# DC-DC_15V_24V.net
KiCad netlist of a schematic drawn in Altium Designer
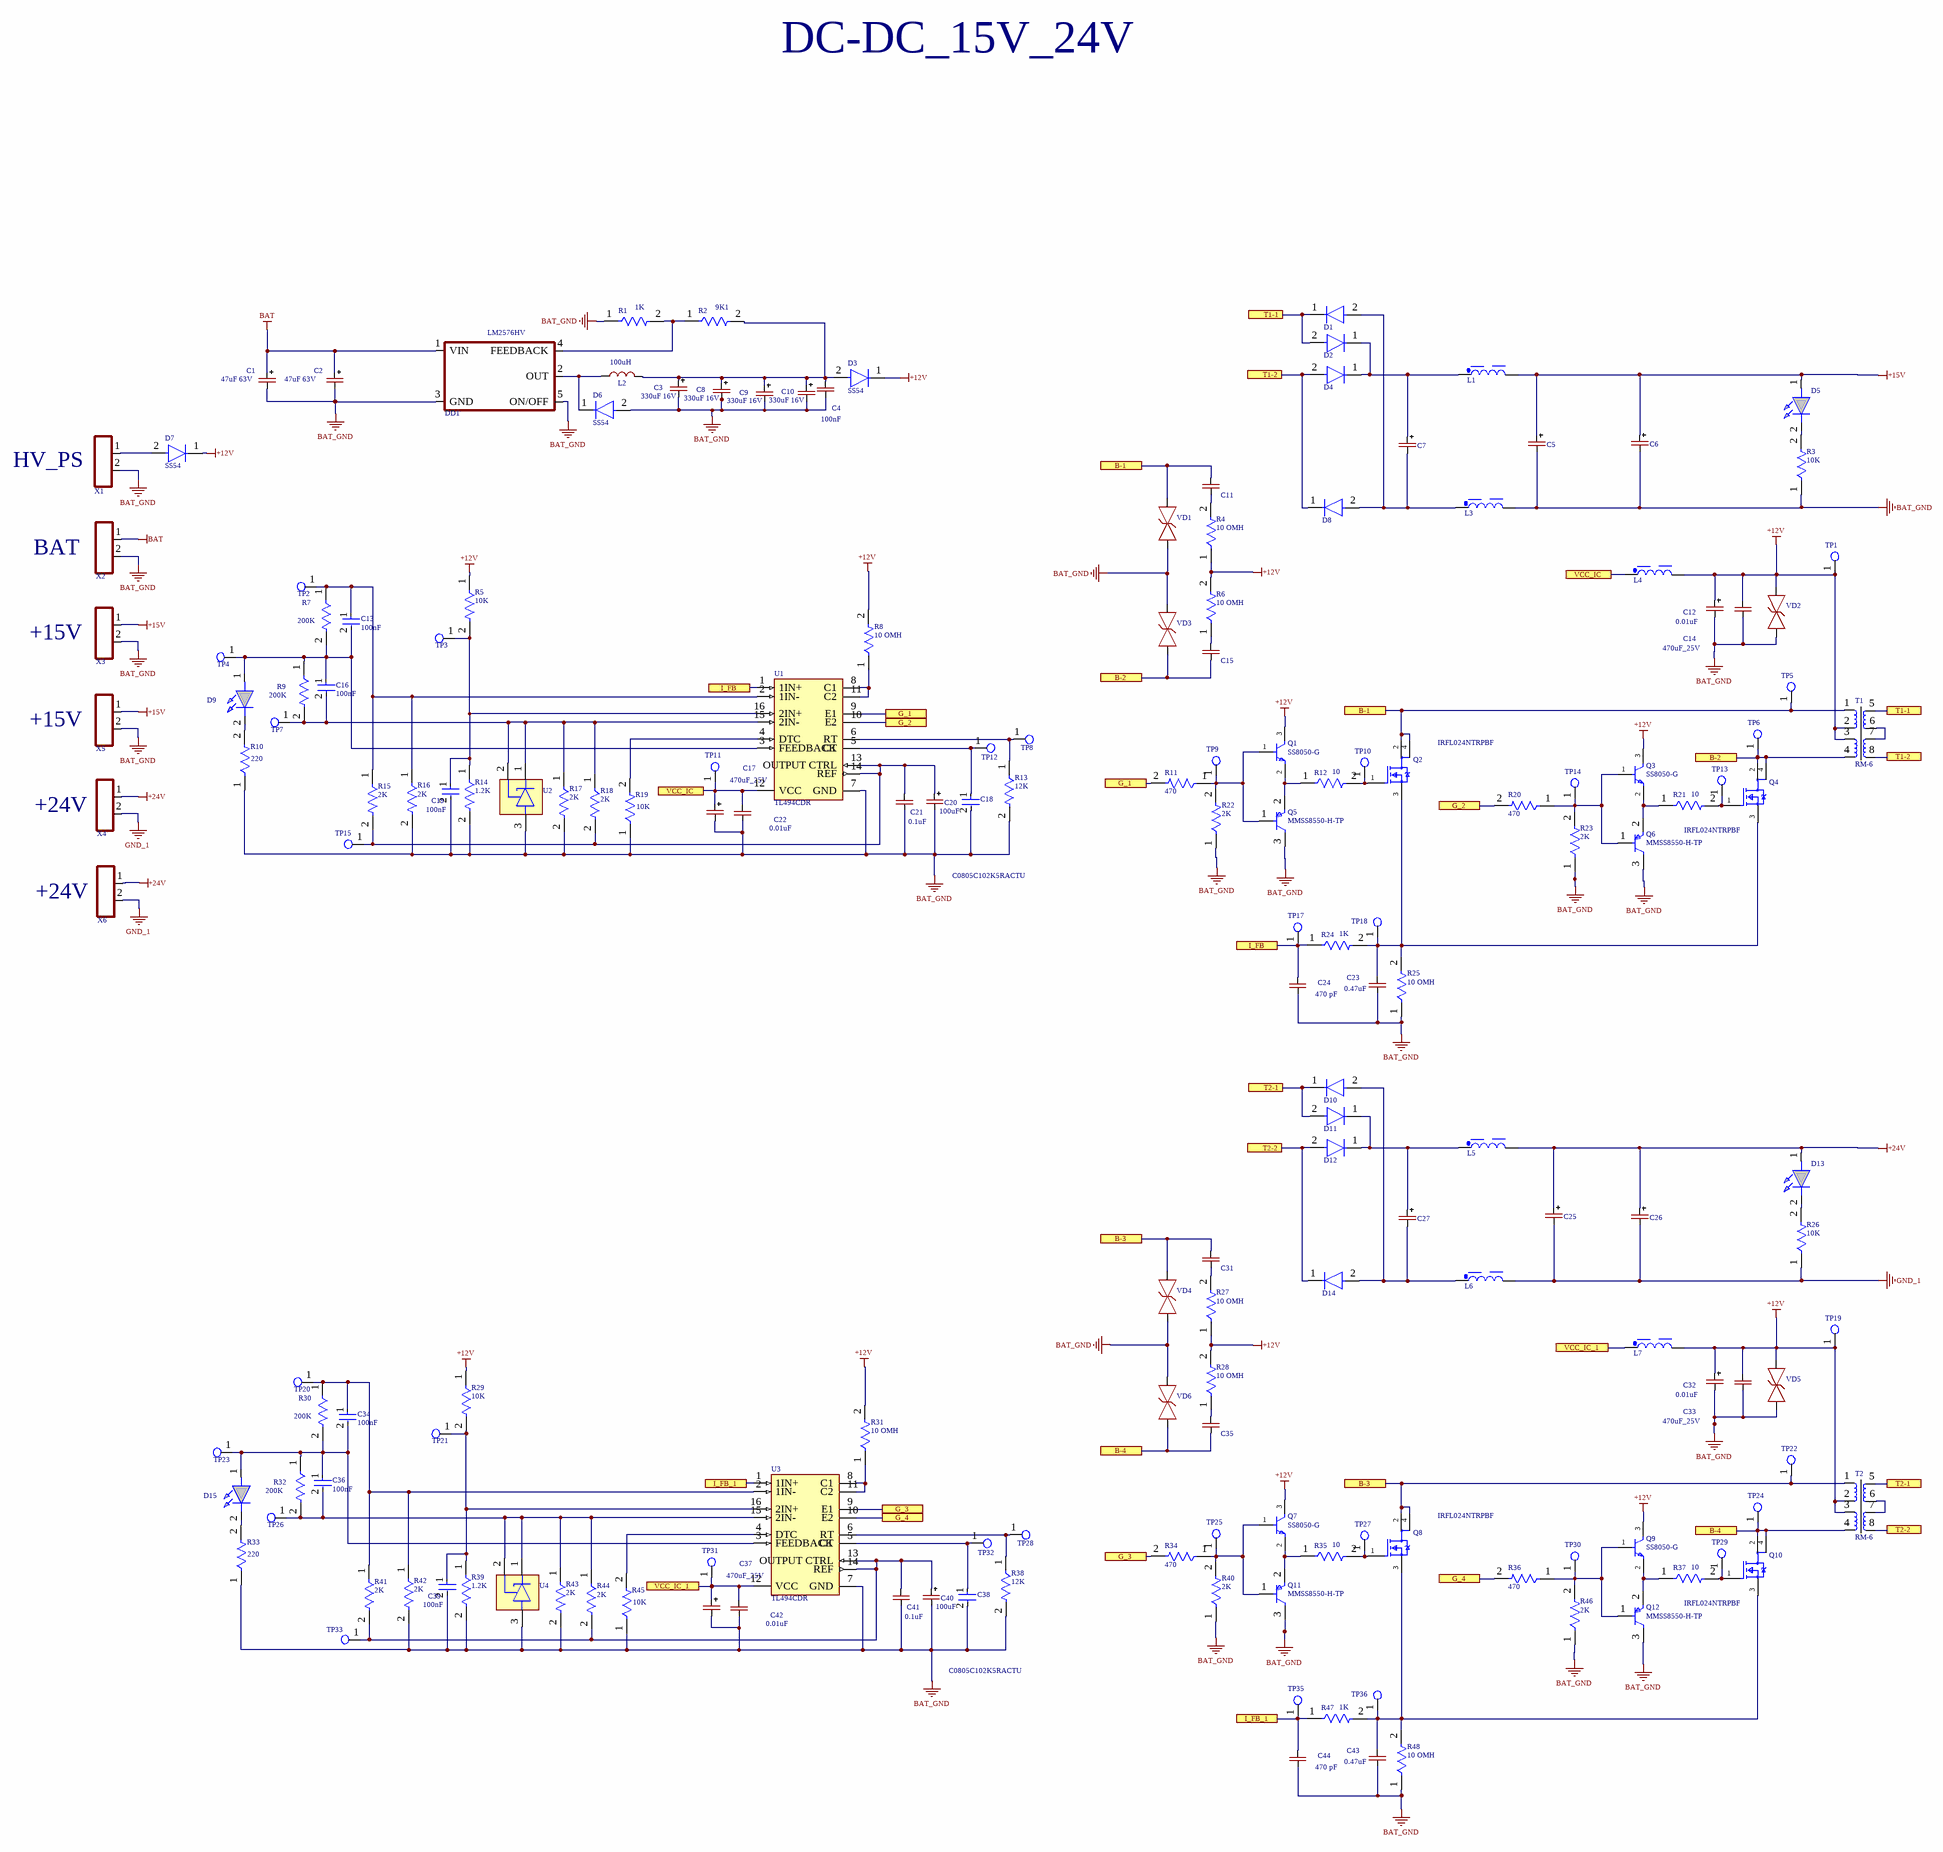
[diagram p0: DC-DC_15V_24V.SchDoc]

(export (version "E")
  (design (tool "Eeschema 10.0.6"))
  (components
    (comp (ref "C1")
      (value "47uF 63V")
      (footprint "CAP_SMD_Size_E")
      (libsource (lib "PASSIVE_COMPONENTS") (part "CAP_POL_SMD"))
    )
    (comp (ref "C2")
      (value "47uF 63V")
      (footprint "CAP_SMD_Size_E")
      (libsource (lib "PASSIVE_COMPONENTS") (part "CAP_POL_SMD"))
    )
    (comp (ref "C3")
      (value "330uF 16V")
      (footprint "CAP_SMD_Size_E")
      (libsource (lib "PASSIVE_COMPONENTS") (part "CAP_POL_SMD"))
    )
    (comp (ref "C4")
      (value "100nF")
      (footprint "CAP-0805")
      (description "1uF ±10% 50V X5R 0805 Multilayer Ceramic Capacitors MLCC - SMD/SMT RoHS")
      (fields (field (name "PART NUMBER") "CC0805KKX5R9BB105") (field (name "MANUFACTURER") "Yageo"))
      (libsource (lib "Database_Libs2") (part "CAP-NON-POLAR"))
    )
    (comp (ref "C5")
      (value "CAP-POLAR")
      (footprint "CAP_SMD_Size_G")
      (libsource (lib "PASSIVE_COMPONENTS") (part "CAP-POLAR"))
    )
    (comp (ref "C6")
      (value "CAP-POLAR")
      (footprint "CAP_SMD_Size_G")
      (libsource (lib "PASSIVE_COMPONENTS") (part "CAP-POLAR"))
    )
    (comp (ref "C7")
      (value "CAP-POLAR")
      (footprint "CAP_SMD_Size_G")
      (libsource (lib "PASSIVE_COMPONENTS") (part "CAP-POLAR"))
    )
    (comp (ref "C8")
      (value "330uF 16V")
      (footprint "CAP_SMD_Size_E")
      (libsource (lib "PASSIVE_COMPONENTS") (part "CAP_POL_SMD"))
    )
    (comp (ref "C9")
      (value "330uF 16V")
      (footprint "CAP_SMD_Size_E")
      (libsource (lib "PASSIVE_COMPONENTS") (part "CAP_POL_SMD"))
    )
    (comp (ref "C10")
      (value "330uF 16V")
      (footprint "CAP_SMD_Size_E")
      (libsource (lib "PASSIVE_COMPONENTS") (part "CAP_POL_SMD"))
    )
    (comp (ref "C11")
      (value "CAP-V")
      (footprint "CAP-V")
      (libsource (lib "PASSIVE_COMPONENTS") (part "CAP-V"))
    )
    (comp (ref "C12")
      (value "0.01uF")
      (footprint "CAP-0805")
      (libsource (lib "PASSIVE_COMPONENTS") (part "CAP-NON-POLAR"))
    )
    (comp (ref "C13")
      (value "100nF")
      (footprint "FP-C0805C-DN-MFG")
      (description "CAP CER 10000PF 50V X7R 0805")
      (fields
        (field (name "MANUFACTURER PART NUMBER") "C0805C103J5RACTU")
        (field (name "MANUFACTURER") "KEMET")
      )
      (libsource (lib "Altium Content Vault") (part "b4654b650e69147ec39a6b967a45e02"))
    )
    (comp (ref "C14")
      (value "470uF_25V")
      (footprint "CAP_SMD_Size_G")
      (libsource (lib "PASSIVE_COMPONENTS") (part "CAP-POLAR"))
    )
    (comp (ref "C15")
      (value "CAP-V")
      (footprint "CAP-V")
      (libsource (lib "PASSIVE_COMPONENTS") (part "CAP-V"))
    )
    (comp (ref "C16")
      (value "100nF")
      (footprint "FP-C0805C-DN-MFG")
      (description "CAP CER 10000PF 50V X7R 0805")
      (fields
        (field (name "MANUFACTURER PART NUMBER") "C0805C103J5RACTU")
        (field (name "MANUFACTURER") "KEMET")
      )
      (libsource (lib "Altium Content Vault") (part "b4654b650e69147ec39a6b967a45e02"))
    )
    (comp (ref "C17")
      (value "470uF_25V")
      (footprint "CAP_SMD_Size_G")
      (libsource (lib "PASSIVE_COMPONENTS") (part "CAP-POLAR"))
    )
    (comp (ref "C18")
      (value "C0805C102K5RACTU")
      (footprint "FP-C0805C-DN-MFG")
      (description "CAP CER 1000PF 50V X7R 0805")
      (fields
        (field (name "OCTOPART") "https://octopart.com/c0805c102k5ractu-kemet-93010")
        (field (name "TOLERANCE") "0.1")
      )
      (libsource (lib "Altium Content Vault") (part "b4654b650e69147ec39a6b967a45e02"))
    )
    (comp (ref "C19")
      (value "100nF")
      (footprint "FP-C0805C-DN-MFG")
      (description "CAP CER 10000PF 50V X7R 0805")
      (fields
        (field (name "MANUFACTURER PART NUMBER") "C0805C103J5RACTU")
        (field (name "MANUFACTURER") "KEMET")
      )
      (libsource (lib "Altium Content Vault") (part "b4654b650e69147ec39a6b967a45e02"))
    )
    (comp (ref "C20")
      (value "100uF")
      (footprint "CAP-TAN-D")
      (libsource (lib "PASSIVE_COMPONENTS") (part "CAP-POLAR"))
    )
    (comp (ref "C21")
      (value "0.1uF")
      (footprint "CAP-0805")
      (libsource (lib "PASSIVE_COMPONENTS") (part "CAP-NON-POLAR"))
    )
    (comp (ref "C22")
      (value "0.01uF")
      (footprint "CAP-0805")
      (libsource (lib "PASSIVE_COMPONENTS") (part "CAP-NON-POLAR"))
    )
    (comp (ref "C23")
      (value "0.47uF")
      (footprint "CAP-0805")
      (libsource (lib "PASSIVE_COMPONENTS") (part "CAP-NON-POLAR"))
    )
    (comp (ref "C24")
      (value "470 pF")
      (footprint "CAP-0805")
      (libsource (lib "PASSIVE_COMPONENTS") (part "CAP-NON-POLAR"))
    )
    (comp (ref "C25")
      (value "CAP-POLAR")
      (footprint "CAP_SMD_Size_G")
      (libsource (lib "PASSIVE_COMPONENTS") (part "CAP-POLAR"))
    )
    (comp (ref "C26")
      (value "CAP-POLAR")
      (footprint "CAP_SMD_Size_G")
      (libsource (lib "PASSIVE_COMPONENTS") (part "CAP-POLAR"))
    )
    (comp (ref "C27")
      (value "CAP-POLAR")
      (footprint "CAP_SMD_Size_G")
      (libsource (lib "PASSIVE_COMPONENTS") (part "CAP-POLAR"))
    )
    (comp (ref "C31")
      (value "CAP-V")
      (footprint "CAP-V")
      (libsource (lib "PASSIVE_COMPONENTS") (part "CAP-V"))
    )
    (comp (ref "C32")
      (value "0.01uF")
      (footprint "CAP-0805")
      (libsource (lib "PASSIVE_COMPONENTS") (part "CAP-NON-POLAR"))
    )
    (comp (ref "C33")
      (value "470uF_25V")
      (footprint "CAP_SMD_Size_G")
      (libsource (lib "PASSIVE_COMPONENTS") (part "CAP-POLAR"))
    )
    (comp (ref "C34")
      (value "100nF")
      (footprint "FP-C0805C-DN-MFG")
      (description "CAP CER 10000PF 50V X7R 0805")
      (fields
        (field (name "MANUFACTURER PART NUMBER") "C0805C103J5RACTU")
        (field (name "MANUFACTURER") "KEMET")
      )
      (libsource (lib "Altium Content Vault") (part "b4654b650e69147ec39a6b967a45e02"))
    )
    (comp (ref "C35")
      (value "CAP-V")
      (footprint "CAP-V")
      (libsource (lib "PASSIVE_COMPONENTS") (part "CAP-V"))
    )
    (comp (ref "C36")
      (value "100nF")
      (footprint "FP-C0805C-DN-MFG")
      (description "CAP CER 10000PF 50V X7R 0805")
      (fields
        (field (name "MANUFACTURER PART NUMBER") "C0805C103J5RACTU")
        (field (name "MANUFACTURER") "KEMET")
      )
      (libsource (lib "Altium Content Vault") (part "b4654b650e69147ec39a6b967a45e02"))
    )
    (comp (ref "C37")
      (value "470uF_25V")
      (footprint "CAP_SMD_Size_G")
      (libsource (lib "PASSIVE_COMPONENTS") (part "CAP-POLAR"))
    )
    (comp (ref "C38")
      (value "C0805C102K5RACTU")
      (footprint "FP-C0805C-DN-MFG")
      (description "CAP CER 1000PF 50V X7R 0805")
      (fields
        (field (name "OCTOPART") "https://octopart.com/c0805c102k5ractu-kemet-93010")
        (field (name "TOLERANCE") "0.1")
      )
      (libsource (lib "Altium Content Vault") (part "b4654b650e69147ec39a6b967a45e02"))
    )
    (comp (ref "C39")
      (value "100nF")
      (footprint "FP-C0805C-DN-MFG")
      (description "CAP CER 10000PF 50V X7R 0805")
      (fields
        (field (name "MANUFACTURER PART NUMBER") "C0805C103J5RACTU")
        (field (name "MANUFACTURER") "KEMET")
      )
      (libsource (lib "Altium Content Vault") (part "b4654b650e69147ec39a6b967a45e02"))
    )
    (comp (ref "C40")
      (value "100uF")
      (footprint "CAP-TAN-D")
      (libsource (lib "PASSIVE_COMPONENTS") (part "CAP-POLAR"))
    )
    (comp (ref "C41")
      (value "0.1uF")
      (footprint "CAP-0805")
      (libsource (lib "PASSIVE_COMPONENTS") (part "CAP-NON-POLAR"))
    )
    (comp (ref "C42")
      (value "0.01uF")
      (footprint "CAP-0805")
      (libsource (lib "PASSIVE_COMPONENTS") (part "CAP-NON-POLAR"))
    )
    (comp (ref "C43")
      (value "0.47uF")
      (footprint "CAP-0805")
      (libsource (lib "PASSIVE_COMPONENTS") (part "CAP-NON-POLAR"))
    )
    (comp (ref "C44")
      (value "470 pF")
      (footprint "CAP-0805")
      (libsource (lib "PASSIVE_COMPONENTS") (part "CAP-NON-POLAR"))
    )
    (comp (ref "D1") (value "US1G") (footprint "DO-214AA") (libsource (lib "Diodes") (part "US1G")))
    (comp (ref "D2") (value "US1G") (footprint "DO-214AA") (libsource (lib "Diodes") (part "US1G")))
    (comp (ref "D3")
      (value "SS54")
      (footprint "DO214-AB")
      (description "ES3D-DO214AB")
      (libsource (lib "Diodes") (part "ES3D-DO214AB"))
    )
    (comp (ref "D4") (value "US1G") (footprint "DO-214AA") (libsource (lib "Diodes") (part "US1G")))
    (comp (ref "D5")
      (value "151031YS06000")
      (footprint "LED_RED")
      (description "WURTH ELEKTRONIK - 151031YS06000 - LED, Yellow, Through Hole, T-1 (3mm), 30 mA, 2 V, 590 nm")
      (fields (field (name "MOUSER PART NUMBER") "710-151031YS06000"))
      (libsource (lib "Optic-LED") (part "LED"))
    )
    (comp (ref "D6")
      (value "SS54")
      (footprint "DO214-AB")
      (description "ES3D-DO214AB")
      (libsource (lib "Diodes") (part "ES3D-DO214AB"))
    )
    (comp (ref "D7")
      (value "SS54")
      (footprint "DO214-AB")
      (description "ES3D-DO214AB")
      (libsource (lib "Diodes") (part "ES3D-DO214AB"))
    )
    (comp (ref "D8") (value "US1G") (footprint "DO-214AA") (libsource (lib "Diodes") (part "US1G")))
    (comp (ref "D9")
      (value "151031YS06000")
      (footprint "LED_RED")
      (description "WURTH ELEKTRONIK - 151031YS06000 - LED, Yellow, Through Hole, T-1 (3mm), 30 mA, 2 V, 590 nm")
      (fields (field (name "MOUSER PART NUMBER") "710-151031YS06000"))
      (libsource (lib "Optic-LED") (part "LED"))
    )
    (comp (ref "D10") (value "US1G") (footprint "DO-214AA") (libsource (lib "Diodes") (part "US1G")))
    (comp (ref "D11") (value "US1G") (footprint "DO-214AA") (libsource (lib "Diodes") (part "US1G")))
    (comp (ref "D12") (value "US1G") (footprint "DO-214AA") (libsource (lib "Diodes") (part "US1G")))
    (comp (ref "D13")
      (value "151031YS06000")
      (footprint "LED_RED")
      (description "WURTH ELEKTRONIK - 151031YS06000 - LED, Yellow, Through Hole, T-1 (3mm), 30 mA, 2 V, 590 nm")
      (fields (field (name "MOUSER PART NUMBER") "710-151031YS06000"))
      (libsource (lib "Optic-LED") (part "LED"))
    )
    (comp (ref "D14") (value "US1G") (footprint "DO-214AA") (libsource (lib "Diodes") (part "US1G")))
    (comp (ref "D15")
      (value "151031YS06000")
      (footprint "LED_RED")
      (description "WURTH ELEKTRONIK - 151031YS06000 - LED, Yellow, Through Hole, T-1 (3mm), 30 mA, 2 V, 590 nm")
      (fields (field (name "MOUSER PART NUMBER") "710-151031YS06000"))
      (libsource (lib "Optic-LED") (part "LED"))
    )
    (comp (ref "DD1")
      (value "LM2576HV")
      (footprint "TO-263-5")
      (libsource (lib "LM2576HV") (part "LM2576HV"))
    )
    (comp (ref "L1")
      (value "390µH, 0.38A")
      (footprint "WE-PD2_7850")
      (description "WE-PD2 SMT Power Inductor, size 7850, 390µH, 0.38A, 1.77Ω")
      (fields
        (field (name "MANUFACTURER PART NUMBER") "744775239")
        (field (name "MANUFACTURER") "Wurth Elektronik")
      )
      (libsource (lib "WE-PD2 (rev22d)") (part "744775239"))
    )
    (comp (ref "L2") (value "100uH") (footprint "CDRH127") (libsource (lib "CDRH127") (part "IND-CONST")))
    (comp (ref "L3")
      (value "390µH, 0.38A")
      (footprint "WE-PD2_7850")
      (description "WE-PD2 SMT Power Inductor, size 7850, 390µH, 0.38A, 1.77Ω")
      (fields
        (field (name "MANUFACTURER PART NUMBER") "744775239")
        (field (name "MANUFACTURER") "Wurth Elektronik")
      )
      (libsource (lib "WE-PD2 (rev22d)") (part "744775239"))
    )
    (comp (ref "L4")
      (value "390µH, 0.38A")
      (footprint "WE-PD2_7850")
      (description "WE-PD2 SMT Power Inductor, size 7850, 390µH, 0.38A, 1.77Ω")
      (fields
        (field (name "MANUFACTURER PART NUMBER") "744775239")
        (field (name "MANUFACTURER") "Wurth Elektronik")
      )
      (libsource (lib "WE-PD2 (rev22d)") (part "744775239"))
    )
    (comp (ref "L5")
      (value "390µH, 0.38A")
      (footprint "WE-PD2_7850")
      (description "WE-PD2 SMT Power Inductor, size 7850, 390µH, 0.38A, 1.77Ω")
      (fields
        (field (name "MANUFACTURER PART NUMBER") "744775239")
        (field (name "MANUFACTURER") "Wurth Elektronik")
      )
      (libsource (lib "WE-PD2 (rev22d)") (part "744775239"))
    )
    (comp (ref "L6")
      (value "390µH, 0.38A")
      (footprint "WE-PD2_7850")
      (description "WE-PD2 SMT Power Inductor, size 7850, 390µH, 0.38A, 1.77Ω")
      (fields
        (field (name "MANUFACTURER PART NUMBER") "744775239")
        (field (name "MANUFACTURER") "Wurth Elektronik")
      )
      (libsource (lib "WE-PD2 (rev22d)") (part "744775239"))
    )
    (comp (ref "L7")
      (value "390µH, 0.38A")
      (footprint "WE-PD2_7850")
      (description "WE-PD2 SMT Power Inductor, size 7850, 390µH, 0.38A, 1.77Ω")
      (fields
        (field (name "MANUFACTURER PART NUMBER") "744775239")
        (field (name "MANUFACTURER") "Wurth Elektronik")
      )
      (libsource (lib "WE-PD2 (rev22d)") (part "744775239"))
    )
    (comp (ref "Q1")
      (value "SS8050-G")
      (footprint "FP-SS8050-G-MFG")
      (description "NPN TRANSISTOR 1.5A 40V SOT-23 R")
      (libsource (lib "Altium Content Vault") (part "2a1388f82443b098dcd57d24ac7632d"))
    )
    (comp (ref "Q2")
      (value "IRFL024NTRPBF")
      (footprint "FP-PG-SOT223-3-IPC_B")
      (description "MOSFET N-CH 55V 2.8A SOT223")
      (libsource (lib "Altium Content Vault") (part "7f70c8421781a2c4d0598199639518f"))
    )
    (comp (ref "Q3")
      (value "SS8050-G")
      (footprint "FP-SS8050-G-MFG")
      (description "NPN TRANSISTOR 1.5A 40V SOT-23 R")
      (libsource (lib "Altium Content Vault") (part "2a1388f82443b098dcd57d24ac7632d"))
    )
    (comp (ref "Q4")
      (value "IRFL024NTRPBF")
      (footprint "FP-PG-SOT223-3-IPC_B")
      (description "MOSFET N-CH 55V 2.8A SOT223")
      (libsource (lib "Altium Content Vault") (part "7f70c8421781a2c4d0598199639518f"))
    )
    (comp (ref "Q5")
      (value "MMSS8550-H-TP")
      (footprint "FP-SOT-23-IPC_B")
      (description "TRANS PNP 25V 1.5A SOT23")
      (libsource (lib "Altium Content Vault") (part "0e8486ed3b47d9c69b8404ba87cf0f7"))
    )
    (comp (ref "Q6")
      (value "MMSS8550-H-TP")
      (footprint "FP-SOT-23-IPC_B")
      (description "TRANS PNP 25V 1.5A SOT23")
      (libsource (lib "Altium Content Vault") (part "0e8486ed3b47d9c69b8404ba87cf0f7"))
    )
    (comp (ref "Q7")
      (value "SS8050-G")
      (footprint "FP-SS8050-G-MFG")
      (description "NPN TRANSISTOR 1.5A 40V SOT-23 R")
      (libsource (lib "Altium Content Vault") (part "2a1388f82443b098dcd57d24ac7632d"))
    )
    (comp (ref "Q8")
      (value "IRFL024NTRPBF")
      (footprint "FP-PG-SOT223-3-IPC_B")
      (description "MOSFET N-CH 55V 2.8A SOT223")
      (libsource (lib "Altium Content Vault") (part "7f70c8421781a2c4d0598199639518f"))
    )
    (comp (ref "Q9")
      (value "SS8050-G")
      (footprint "FP-SS8050-G-MFG")
      (description "NPN TRANSISTOR 1.5A 40V SOT-23 R")
      (libsource (lib "Altium Content Vault") (part "2a1388f82443b098dcd57d24ac7632d"))
    )
    (comp (ref "Q10")
      (value "IRFL024NTRPBF")
      (footprint "FP-PG-SOT223-3-IPC_B")
      (description "MOSFET N-CH 55V 2.8A SOT223")
      (libsource (lib "Altium Content Vault") (part "7f70c8421781a2c4d0598199639518f"))
    )
    (comp (ref "Q11")
      (value "MMSS8550-H-TP")
      (footprint "FP-SOT-23-IPC_B")
      (description "TRANS PNP 25V 1.5A SOT23")
      (libsource (lib "Altium Content Vault") (part "0e8486ed3b47d9c69b8404ba87cf0f7"))
    )
    (comp (ref "Q12")
      (value "MMSS8550-H-TP")
      (footprint "FP-SOT-23-IPC_B")
      (description "TRANS PNP 25V 1.5A SOT23")
      (libsource (lib "Altium Content Vault") (part "0e8486ed3b47d9c69b8404ba87cf0f7"))
    )
    (comp (ref "R1")
      (value "1K")
      (footprint "RES-0805")
      (description "10K")
      (libsource (lib "PASSIVE_COMPONENTS") (part "RES-CONST"))
    )
    (comp (ref "R2")
      (value "9K1")
      (footprint "RES-0805")
      (description "10K")
      (libsource (lib "PASSIVE_COMPONENTS") (part "RES-CONST"))
    )
    (comp (ref "R3")
      (value "10K")
      (footprint "RES-0805")
      (libsource (lib "PASSIVE_COMPONENTS") (part "RES-CONST"))
    )
    (comp (ref "R4")
      (value "10 OMH")
      (footprint "RES-1206")
      (libsource (lib "PASSIVE_COMPONENTS") (part "RES-CONST"))
    )
    (comp (ref "R5")
      (value "10K")
      (footprint "FP-CRCW0805-e3-MFG")
      (description "RES Thick Film, 2kΩ, 1%, 0.125W, 100ppm/°C, 0805")
      (fields (field (name "TOLERANCE") "1%"))
      (libsource (lib "Pasive_components") (part "CMP-2001-04908-2"))
    )
    (comp (ref "R6")
      (value "10 OMH")
      (footprint "RES-1206")
      (libsource (lib "PASSIVE_COMPONENTS") (part "RES-CONST"))
    )
    (comp (ref "R7")
      (value "200K")
      (footprint "FP-CRCW0805-e3-MFG")
      (description "RES Thick Film, 2kΩ, 1%, 0.125W, 100ppm/°C, 0805")
      (fields (field (name "TOLERANCE") "1%"))
      (libsource (lib "Pasive_components") (part "CMP-2001-04908-2"))
    )
    (comp (ref "R8")
      (value "10 OMH")
      (footprint "RES-1206")
      (libsource (lib "PASSIVE_COMPONENTS") (part "RES-CONST"))
    )
    (comp (ref "R9")
      (value "200K")
      (footprint "FP-CRCW0805-e3-MFG")
      (description "RES Thick Film, 2kΩ, 1%, 0.125W, 100ppm/°C, 0805")
      (fields (field (name "TOLERANCE") "1%"))
      (libsource (lib "Pasive_components") (part "CMP-2001-04908-2"))
    )
    (comp (ref "R10")
      (value "220")
      (footprint "RES-0805")
      (libsource (lib "PASSIVE_COMPONENTS") (part "RES-CONST"))
    )
    (comp (ref "R11")
      (value "470")
      (footprint "RES-0805")
      (libsource (lib "PASSIVE_COMPONENTS") (part "RES-CONST"))
    )
    (comp (ref "R12")
      (value "10")
      (footprint "RES-0805")
      (libsource (lib "PASSIVE_COMPONENTS") (part "RES-CONST"))
    )
    (comp (ref "R13")
      (value "12K")
      (footprint "FP-CRCW0805-e3-MFG")
      (description "RES Thick Film, 12kΩ, 1%, 0.125W, 100ppm/°C, 0805")
      (fields (field (name "TOLERANCE") "1%"))
      (libsource (lib "Pasive_components") (part "CMP-2001-04908-2"))
    )
    (comp (ref "R14")
      (value "1.2K")
      (footprint "FP-CRCW0805-e3-MFG")
      (description "RES Thick Film, 2kΩ, 1%, 0.125W, 100ppm/°C, 0805")
      (fields (field (name "TOLERANCE") "1%"))
      (libsource (lib "Pasive_components") (part "CMP-2001-04908-2"))
    )
    (comp (ref "R15")
      (value "2K")
      (footprint "FP-CRCW0805-e3-MFG")
      (description "RES Thick Film, 2kΩ, 1%, 0.125W, 100ppm/°C, 0805")
      (fields (field (name "TOLERANCE") "1%"))
      (libsource (lib "Pasive_components") (part "CMP-2001-04908-2"))
    )
    (comp (ref "R16")
      (value "2K")
      (footprint "FP-CRCW0805-e3-MFG")
      (description "RES Thick Film, 82kΩ, 1%, 0.125W, 100ppm/°C, 0805")
      (fields (field (name "TOLERANCE") "1%"))
      (libsource (lib "Pasive_components") (part "CMP-2001-04908-2"))
    )
    (comp (ref "R17")
      (value "2K")
      (footprint "FP-CRCW0805-e3-MFG")
      (description "RES Thick Film, 2kΩ, 1%, 0.125W, 100ppm/°C, 0805")
      (fields (field (name "TOLERANCE") "1%"))
      (libsource (lib "Pasive_components") (part "CMP-2001-04908-2"))
    )
    (comp (ref "R18")
      (value "2K")
      (footprint "FP-CRCW0805-e3-MFG")
      (description "RES Thick Film, 2kΩ, 1%, 0.125W, 100ppm/°C, 0805")
      (fields (field (name "TOLERANCE") "1%"))
      (libsource (lib "Pasive_components") (part "CMP-2001-04908-2"))
    )
    (comp (ref "R19")
      (value "10K")
      (footprint "RES-0805")
      (libsource (lib "PASSIVE_COMPONENTS") (part "RES-CONST"))
    )
    (comp (ref "R20")
      (value "470")
      (footprint "RES-0805")
      (libsource (lib "PASSIVE_COMPONENTS") (part "RES-CONST"))
    )
    (comp (ref "R21")
      (value "10")
      (footprint "RES-0805")
      (libsource (lib "PASSIVE_COMPONENTS") (part "RES-CONST"))
    )
    (comp (ref "R22")
      (value "2K")
      (footprint "RES-0805")
      (libsource (lib "PASSIVE_COMPONENTS") (part "RES-CONST"))
    )
    (comp (ref "R23")
      (value "2K")
      (footprint "RES-0805")
      (libsource (lib "PASSIVE_COMPONENTS") (part "RES-CONST"))
    )
    (comp (ref "R24")
      (value "1K")
      (footprint "RES-0805")
      (libsource (lib "PASSIVE_COMPONENTS") (part "RES-CONST"))
    )
    (comp (ref "R25")
      (value "10 OMH")
      (footprint "RES-2512")
      (libsource (lib "PASSIVE_COMPONENTS") (part "RES-CONST"))
    )
    (comp (ref "R26")
      (value "10K")
      (footprint "RES-0805")
      (libsource (lib "PASSIVE_COMPONENTS") (part "RES-CONST"))
    )
    (comp (ref "R27")
      (value "10 OMH")
      (footprint "RES-1206")
      (libsource (lib "PASSIVE_COMPONENTS") (part "RES-CONST"))
    )
    (comp (ref "R28")
      (value "10 OMH")
      (footprint "RES-1206")
      (libsource (lib "PASSIVE_COMPONENTS") (part "RES-CONST"))
    )
    (comp (ref "R29")
      (value "10K")
      (footprint "FP-CRCW0805-e3-MFG")
      (description "RES Thick Film, 2kΩ, 1%, 0.125W, 100ppm/°C, 0805")
      (fields (field (name "TOLERANCE") "1%"))
      (libsource (lib "Pasive_components") (part "CMP-2001-04908-2"))
    )
    (comp (ref "R30")
      (value "200K")
      (footprint "FP-CRCW0805-e3-MFG")
      (description "RES Thick Film, 2kΩ, 1%, 0.125W, 100ppm/°C, 0805")
      (fields (field (name "TOLERANCE") "1%"))
      (libsource (lib "Pasive_components") (part "CMP-2001-04908-2"))
    )
    (comp (ref "R31")
      (value "10 OMH")
      (footprint "RES-1206")
      (libsource (lib "PASSIVE_COMPONENTS") (part "RES-CONST"))
    )
    (comp (ref "R32")
      (value "200K")
      (footprint "FP-CRCW0805-e3-MFG")
      (description "RES Thick Film, 2kΩ, 1%, 0.125W, 100ppm/°C, 0805")
      (fields (field (name "TOLERANCE") "1%"))
      (libsource (lib "Pasive_components") (part "CMP-2001-04908-2"))
    )
    (comp (ref "R33")
      (value "220")
      (footprint "RES-0805")
      (libsource (lib "PASSIVE_COMPONENTS") (part "RES-CONST"))
    )
    (comp (ref "R34")
      (value "470")
      (footprint "RES-0805")
      (libsource (lib "PASSIVE_COMPONENTS") (part "RES-CONST"))
    )
    (comp (ref "R35")
      (value "10")
      (footprint "RES-0805")
      (libsource (lib "PASSIVE_COMPONENTS") (part "RES-CONST"))
    )
    (comp (ref "R36")
      (value "470")
      (footprint "RES-0805")
      (libsource (lib "PASSIVE_COMPONENTS") (part "RES-CONST"))
    )
    (comp (ref "R37")
      (value "10")
      (footprint "RES-0805")
      (libsource (lib "PASSIVE_COMPONENTS") (part "RES-CONST"))
    )
    (comp (ref "R38")
      (value "12K")
      (footprint "FP-CRCW0805-e3-MFG")
      (description "RES Thick Film, 12kΩ, 1%, 0.125W, 100ppm/°C, 0805")
      (fields (field (name "TOLERANCE") "1%"))
      (libsource (lib "Pasive_components") (part "CMP-2001-04908-2"))
    )
    (comp (ref "R39")
      (value "1.2K")
      (footprint "FP-CRCW0805-e3-MFG")
      (description "RES Thick Film, 2kΩ, 1%, 0.125W, 100ppm/°C, 0805")
      (fields (field (name "TOLERANCE") "1%"))
      (libsource (lib "Pasive_components") (part "CMP-2001-04908-2"))
    )
    (comp (ref "R40")
      (value "2K")
      (footprint "RES-0805")
      (libsource (lib "PASSIVE_COMPONENTS") (part "RES-CONST"))
    )
    (comp (ref "R41")
      (value "2K")
      (footprint "FP-CRCW0805-e3-MFG")
      (description "RES Thick Film, 2kΩ, 1%, 0.125W, 100ppm/°C, 0805")
      (fields (field (name "TOLERANCE") "1%"))
      (libsource (lib "Pasive_components") (part "CMP-2001-04908-2"))
    )
    (comp (ref "R42")
      (value "2K")
      (footprint "FP-CRCW0805-e3-MFG")
      (description "RES Thick Film, 82kΩ, 1%, 0.125W, 100ppm/°C, 0805")
      (fields (field (name "TOLERANCE") "1%"))
      (libsource (lib "Pasive_components") (part "CMP-2001-04908-2"))
    )
    (comp (ref "R43")
      (value "2K")
      (footprint "FP-CRCW0805-e3-MFG")
      (description "RES Thick Film, 2kΩ, 1%, 0.125W, 100ppm/°C, 0805")
      (fields (field (name "TOLERANCE") "1%"))
      (libsource (lib "Pasive_components") (part "CMP-2001-04908-2"))
    )
    (comp (ref "R44")
      (value "2K")
      (footprint "FP-CRCW0805-e3-MFG")
      (description "RES Thick Film, 2kΩ, 1%, 0.125W, 100ppm/°C, 0805")
      (fields (field (name "TOLERANCE") "1%"))
      (libsource (lib "Pasive_components") (part "CMP-2001-04908-2"))
    )
    (comp (ref "R45")
      (value "10K")
      (footprint "RES-0805")
      (libsource (lib "PASSIVE_COMPONENTS") (part "RES-CONST"))
    )
    (comp (ref "R46")
      (value "2K")
      (footprint "RES-0805")
      (libsource (lib "PASSIVE_COMPONENTS") (part "RES-CONST"))
    )
    (comp (ref "R47")
      (value "1K")
      (footprint "RES-0805")
      (libsource (lib "PASSIVE_COMPONENTS") (part "RES-CONST"))
    )
    (comp (ref "R48")
      (value "10 OMH")
      (footprint "RES-2512")
      (libsource (lib "PASSIVE_COMPONENTS") (part "RES-CONST"))
    )
    (comp (ref "T1")
      (value "RM-6")
      (footprint "TRANS_RM6")
      (libsource (lib "Transformers") (part "RM_6_12-12-18-18"))
    )
    (comp (ref "T2")
      (value "RM-6")
      (footprint "TRANS_RM6")
      (libsource (lib "Transformers") (part "RM_6_12-12-18-18"))
    )
    (comp (ref "TP1")
      (value "~")
      (footprint "Test_Point")
      (description "Test_Point")
      (libsource (lib "Connectors") (part "TP_PCB?"))
    )
    (comp (ref "TP2")
      (value "Test_Point_PCB")
      (footprint "Test_Point")
      (description "Test_Point")
      (libsource (lib "Test_Point") (part "TP_PCB?"))
    )
    (comp (ref "TP3")
      (value "Test_Point_PCB")
      (footprint "Test_Point")
      (description "Test_Point")
      (libsource (lib "Test_Point") (part "TP_PCB?"))
    )
    (comp (ref "TP4")
      (value "Test_Point_PCB")
      (footprint "Test_Point")
      (description "Test_Point")
      (libsource (lib "Test_Point") (part "TP_PCB?"))
    )
    (comp (ref "TP5")
      (value "~")
      (footprint "Test_Point")
      (description "Test_Point")
      (libsource (lib "Connectors") (part "TP_PCB?"))
    )
    (comp (ref "TP6")
      (value "~")
      (footprint "Test_Point")
      (description "Test_Point")
      (libsource (lib "Connectors") (part "TP_PCB?"))
    )
    (comp (ref "TP7")
      (value "~")
      (footprint "Test_Point")
      (description "Test_Point")
      (libsource (lib "Connectors") (part "TP_PCB?"))
    )
    (comp (ref "TP8")
      (value "~")
      (footprint "Test_Point")
      (description "Test_Point")
      (libsource (lib "Connectors") (part "TP_PCB?"))
    )
    (comp (ref "TP9")
      (value "~")
      (footprint "Test_Point")
      (description "Test_Point")
      (libsource (lib "Connectors") (part "TP_PCB?"))
    )
    (comp (ref "TP10")
      (value "~")
      (footprint "Test_Point")
      (description "Test_Point")
      (libsource (lib "Connectors") (part "TP_PCB?"))
    )
    (comp (ref "TP11")
      (value "~")
      (footprint "Test_Point")
      (description "Test_Point")
      (libsource (lib "Connectors") (part "TP_PCB?"))
    )
    (comp (ref "TP12")
      (value "Test_Point_PCB")
      (footprint "Test_Point")
      (description "Test_Point")
      (libsource (lib "Test_Point") (part "TP_PCB?"))
    )
    (comp (ref "TP13")
      (value "~")
      (footprint "Test_Point")
      (description "Test_Point")
      (libsource (lib "Connectors") (part "TP_PCB?"))
    )
    (comp (ref "TP14")
      (value "~")
      (footprint "Test_Point")
      (description "Test_Point")
      (libsource (lib "Connectors") (part "TP_PCB?"))
    )
    (comp (ref "TP15")
      (value "Test_Point_PCB")
      (footprint "Test_Point")
      (description "Test_Point")
      (libsource (lib "Test_Point") (part "TP_PCB?"))
    )
    (comp (ref "TP17")
      (value "~")
      (footprint "Test_Point")
      (description "Test_Point")
      (libsource (lib "Connectors") (part "TP_PCB?"))
    )
    (comp (ref "TP18")
      (value "~")
      (footprint "Test_Point")
      (description "Test_Point")
      (libsource (lib "Connectors") (part "TP_PCB?"))
    )
    (comp (ref "TP19")
      (value "~")
      (footprint "Test_Point")
      (description "Test_Point")
      (libsource (lib "Connectors") (part "TP_PCB?"))
    )
    (comp (ref "TP20")
      (value "Test_Point_PCB")
      (footprint "Test_Point")
      (description "Test_Point")
      (libsource (lib "Test_Point") (part "TP_PCB?"))
    )
    (comp (ref "TP21")
      (value "Test_Point_PCB")
      (footprint "Test_Point")
      (description "Test_Point")
      (libsource (lib "Test_Point") (part "TP_PCB?"))
    )
    (comp (ref "TP22")
      (value "~")
      (footprint "Test_Point")
      (description "Test_Point")
      (libsource (lib "Connectors") (part "TP_PCB?"))
    )
    (comp (ref "TP23")
      (value "Test_Point_PCB")
      (footprint "Test_Point")
      (description "Test_Point")
      (libsource (lib "Test_Point") (part "TP_PCB?"))
    )
    (comp (ref "TP24")
      (value "~")
      (footprint "Test_Point")
      (description "Test_Point")
      (libsource (lib "Connectors") (part "TP_PCB?"))
    )
    (comp (ref "TP25")
      (value "~")
      (footprint "Test_Point")
      (description "Test_Point")
      (libsource (lib "Connectors") (part "TP_PCB?"))
    )
    (comp (ref "TP26")
      (value "~")
      (footprint "Test_Point")
      (description "Test_Point")
      (libsource (lib "Connectors") (part "TP_PCB?"))
    )
    (comp (ref "TP27")
      (value "~")
      (footprint "Test_Point")
      (description "Test_Point")
      (libsource (lib "Connectors") (part "TP_PCB?"))
    )
    (comp (ref "TP28")
      (value "~")
      (footprint "Test_Point")
      (description "Test_Point")
      (libsource (lib "Connectors") (part "TP_PCB?"))
    )
    (comp (ref "TP29")
      (value "~")
      (footprint "Test_Point")
      (description "Test_Point")
      (libsource (lib "Connectors") (part "TP_PCB?"))
    )
    (comp (ref "TP30")
      (value "~")
      (footprint "Test_Point")
      (description "Test_Point")
      (libsource (lib "Connectors") (part "TP_PCB?"))
    )
    (comp (ref "TP31")
      (value "~")
      (footprint "Test_Point")
      (description "Test_Point")
      (libsource (lib "Connectors") (part "TP_PCB?"))
    )
    (comp (ref "TP32")
      (value "Test_Point_PCB")
      (footprint "Test_Point")
      (description "Test_Point")
      (libsource (lib "Test_Point") (part "TP_PCB?"))
    )
    (comp (ref "TP33")
      (value "Test_Point_PCB")
      (footprint "Test_Point")
      (description "Test_Point")
      (libsource (lib "Test_Point") (part "TP_PCB?"))
    )
    (comp (ref "TP35")
      (value "~")
      (footprint "Test_Point")
      (description "Test_Point")
      (libsource (lib "Connectors") (part "TP_PCB?"))
    )
    (comp (ref "TP36")
      (value "~")
      (footprint "Test_Point")
      (description "Test_Point")
      (libsource (lib "Connectors") (part "TP_PCB?"))
    )
    (comp (ref "U1")
      (value "TL494CDR")
      (footprint "D0016A_N")
      (fields (field (name "MANUFACTURER") "Texas Instruments"))
      (libsource (lib "Altium Content Vault") (part "TI-494D16"))
    )
    (comp (ref "U2")
      (value "TL431")
      (footprint "TL431_SOT-23-3(A)")
      (description "TL431_SOT-23-3")
      (libsource (lib "Diodes") (part "TL431_SOT-23-3"))
    )
    (comp (ref "U3")
      (value "TL494CDR")
      (footprint "D0016A_N")
      (fields (field (name "MANUFACTURER") "Texas Instruments"))
      (libsource (lib "Altium Content Vault") (part "TI-494D16"))
    )
    (comp (ref "U4")
      (value "TL431")
      (footprint "TL431_SOT-23-3(A)")
      (description "TL431_SOT-23-3")
      (libsource (lib "Diodes") (part "TL431_SOT-23-3"))
    )
    (comp (ref "VD1")
      (value "Suppressor")
      (footprint "P6KE350CA")
      (libsource (lib "Diodes") (part "Suppressor"))
    )
    (comp (ref "VD2")
      (value "Suppressor")
      (footprint "DO-214AA")
      (libsource (lib "Diodes") (part "Suppressor"))
    )
    (comp (ref "VD3")
      (value "Suppressor")
      (footprint "P6KE350CA")
      (libsource (lib "Diodes") (part "Suppressor"))
    )
    (comp (ref "VD4")
      (value "Suppressor")
      (footprint "P6KE350CA")
      (libsource (lib "Diodes") (part "Suppressor"))
    )
    (comp (ref "VD5")
      (value "Suppressor")
      (footprint "DO-214AA")
      (libsource (lib "Diodes") (part "Suppressor"))
    )
    (comp (ref "VD6")
      (value "Suppressor")
      (footprint "P6KE350CA")
      (libsource (lib "Diodes") (part "Suppressor"))
    )
    (comp (ref "X1") (value "CONN-2-PIN") (footprint "XH2-") (libsource (lib "XH 2PIN") (part "CONN-2-PIN")))
    (comp (ref "X2") (value "CONN-2-PIN") (footprint "XH2-") (libsource (lib "XH 2PIN") (part "CONN-2-PIN")))
    (comp (ref "X3") (value "CONN-2-PIN") (footprint "XH2-") (libsource (lib "XH 2PIN") (part "CONN-2-PIN")))
    (comp (ref "X4") (value "CONN-2-PIN") (footprint "XH2-") (libsource (lib "XH 2PIN") (part "CONN-2-PIN")))
    (comp (ref "X5") (value "CONN-2-PIN") (footprint "XH2-") (libsource (lib "XH 2PIN") (part "CONN-2-PIN")))
    (comp (ref "X6") (value "CONN-2-PIN") (footprint "XH2-") (libsource (lib "XH 2PIN") (part "CONN-2-PIN")))
  )
  (nets
    (net (code "1") (name "+12V") (class "Default")
      (node (ref "C12") (pin "2") (pinfunction "2_2") (pintype "passive"))
      (node (ref "C14") (pin "1") (pinfunction "+_1") (pintype "passive"))
      (node (ref "C32") (pin "2") (pinfunction "2_2") (pintype "passive"))
      (node (ref "C33") (pin "1") (pinfunction "+_1") (pintype "passive"))
      (node (ref "D3") (pin "1") (pinfunction "C_1") (pintype "passive"))
      (node (ref "D7") (pin "1") (pinfunction "C_1") (pintype "passive"))
      (node (ref "L4") (pin "2") (pinfunction "2_2") (pintype "passive"))
      (node (ref "L7") (pin "2") (pinfunction "2_2") (pintype "passive"))
      (node (ref "Q1") (pin "3") (pinfunction "C_3") (pintype "passive"))
      (node (ref "Q3") (pin "3") (pinfunction "C_3") (pintype "passive"))
      (node (ref "Q7") (pin "3") (pinfunction "C_3") (pintype "passive"))
      (node (ref "Q9") (pin "3") (pinfunction "C_3") (pintype "passive"))
      (node (ref "R27") (pin "1") (pinfunction "1_1") (pintype "passive"))
      (node (ref "R28") (pin "2") (pinfunction "2_2") (pintype "passive"))
      (node (ref "R29") (pin "1") (pinfunction "1_1") (pintype "passive"))
      (node (ref "R31") (pin "2") (pinfunction "2_2") (pintype "passive"))
      (node (ref "R4") (pin "1") (pinfunction "1_1") (pintype "passive"))
      (node (ref "R5") (pin "1") (pinfunction "1_1") (pintype "passive"))
      (node (ref "R6") (pin "2") (pinfunction "2_2") (pintype "passive"))
      (node (ref "R8") (pin "2") (pinfunction "2_2") (pintype "passive"))
      (node (ref "T1") (pin "2") (pinfunction "2_2") (pintype "passive"))
      (node (ref "T1") (pin "3") (pinfunction "3_3") (pintype "passive"))
      (node (ref "T2") (pin "2") (pinfunction "2_2") (pintype "passive"))
      (node (ref "T2") (pin "3") (pinfunction "3_3") (pintype "passive"))
      (node (ref "TP1") (pin "1") (pinfunction "G9_1") (pintype "passive"))
      (node (ref "TP19") (pin "1") (pinfunction "G9_1") (pintype "passive"))
      (node (ref "VD2") (pin "2") (pinfunction "A_2") (pintype "passive"))
      (node (ref "VD5") (pin "2") (pinfunction "A_2") (pintype "passive"))
    )
    (net (code "2") (name "+15V") (class "Default")
      (node (ref "C5") (pin "1") (pinfunction "+_1") (pintype "passive"))
      (node (ref "C6") (pin "1") (pinfunction "+_1") (pintype "passive"))
      (node (ref "D5") (pin "1") (pinfunction "A_1") (pintype "passive"))
      (node (ref "L1") (pin "2") (pinfunction "2_2") (pintype "passive"))
      (node (ref "X3") (pin "1") (pinfunction "1_1") (pintype "passive"))
      (node (ref "X5") (pin "1") (pinfunction "1_1") (pintype "passive"))
    )
    (net (code "3") (name "+24V") (class "Default")
      (node (ref "C25") (pin "1") (pinfunction "+_1") (pintype "passive"))
      (node (ref "C26") (pin "1") (pinfunction "+_1") (pintype "passive"))
      (node (ref "D13") (pin "1") (pinfunction "A_1") (pintype "passive"))
      (node (ref "L5") (pin "2") (pinfunction "2_2") (pintype "passive"))
      (node (ref "X4") (pin "1") (pinfunction "1_1") (pintype "passive"))
      (node (ref "X6") (pin "1") (pinfunction "1_1") (pintype "passive"))
    )
    (net (code "4") (name "/B-1") (class "Default")
      (node (ref "C11") (pin "2") (pinfunction "2_2") (pintype "passive"))
      (node (ref "Q2") (pin "2") (pinfunction "D_2") (pintype "passive"))
      (node (ref "Q2") (pin "4") (pinfunction "D_4") (pintype "passive"))
      (node (ref "T1") (pin "1") (pinfunction "1_1") (pintype "passive"))
      (node (ref "TP5") (pin "1") (pinfunction "G9_1") (pintype "passive"))
      (node (ref "VD1") (pin "2") (pinfunction "A_2") (pintype "passive"))
    )
    (net (code "5") (name "/B-2") (class "Default")
      (node (ref "C15") (pin "1") (pinfunction "1_1") (pintype "passive"))
      (node (ref "Q4") (pin "2") (pinfunction "D_2") (pintype "passive"))
      (node (ref "Q4") (pin "4") (pinfunction "D_4") (pintype "passive"))
      (node (ref "T1") (pin "4") (pinfunction "4_4") (pintype "passive"))
      (node (ref "TP6") (pin "1") (pinfunction "G9_1") (pintype "passive"))
      (node (ref "VD3") (pin "1") (pinfunction "C_1") (pintype "passive"))
    )
    (net (code "6") (name "/B-3") (class "Default")
      (node (ref "C31") (pin "2") (pinfunction "2_2") (pintype "passive"))
      (node (ref "Q8") (pin "2") (pinfunction "D_2") (pintype "passive"))
      (node (ref "Q8") (pin "4") (pinfunction "D_4") (pintype "passive"))
      (node (ref "T2") (pin "1") (pinfunction "1_1") (pintype "passive"))
      (node (ref "TP22") (pin "1") (pinfunction "G9_1") (pintype "passive"))
      (node (ref "VD4") (pin "2") (pinfunction "A_2") (pintype "passive"))
    )
    (net (code "7") (name "/B-4") (class "Default")
      (node (ref "C35") (pin "1") (pinfunction "1_1") (pintype "passive"))
      (node (ref "Q10") (pin "2") (pinfunction "D_2") (pintype "passive"))
      (node (ref "Q10") (pin "4") (pinfunction "D_4") (pintype "passive"))
      (node (ref "T2") (pin "4") (pinfunction "4_4") (pintype "passive"))
      (node (ref "TP24") (pin "1") (pinfunction "G9_1") (pintype "passive"))
      (node (ref "VD6") (pin "1") (pinfunction "C_1") (pintype "passive"))
    )
    (net (code "8") (name "/G_1") (class "Default")
      (node (ref "R11") (pin "2") (pinfunction "2_2") (pintype "passive"))
      (node (ref "U1") (pin "9") (pinfunction "E1_9") (pintype "passive"))
    )
    (net (code "9") (name "/G_2") (class "Default")
      (node (ref "R20") (pin "2") (pinfunction "2_2") (pintype "passive"))
      (node (ref "U1") (pin "10") (pinfunction "E2_10") (pintype "passive"))
    )
    (net (code "10") (name "/G_3") (class "Default")
      (node (ref "R34") (pin "2") (pinfunction "2_2") (pintype "passive"))
      (node (ref "U3") (pin "9") (pinfunction "E1_9") (pintype "passive"))
    )
    (net (code "11") (name "/G_4") (class "Default")
      (node (ref "R36") (pin "2") (pinfunction "2_2") (pintype "passive"))
      (node (ref "U3") (pin "10") (pinfunction "E2_10") (pintype "passive"))
    )
    (net (code "12") (name "/I_FB") (class "Default")
      (node (ref "C24") (pin "2") (pinfunction "2_2") (pintype "passive"))
      (node (ref "R24") (pin "1") (pinfunction "1_1") (pintype "passive"))
      (node (ref "TP17") (pin "1") (pinfunction "G9_1") (pintype "passive"))
      (node (ref "U1") (pin "1") (pinfunction "1IN+_1") (pintype "input"))
    )
    (net (code "13") (name "/I_FB_1") (class "Default")
      (node (ref "C44") (pin "2") (pinfunction "2_2") (pintype "passive"))
      (node (ref "R47") (pin "1") (pinfunction "1_1") (pintype "passive"))
      (node (ref "TP35") (pin "1") (pinfunction "G9_1") (pintype "passive"))
      (node (ref "U3") (pin "1") (pinfunction "1IN+_1") (pintype "input"))
    )
    (net (code "14") (name "/T1-1") (class "Default")
      (node (ref "D1") (pin "1") (pinfunction "C_1") (pintype "passive"))
      (node (ref "D2") (pin "2") (pinfunction "A_2") (pintype "passive"))
      (node (ref "T1") (pin "5") (pinfunction "5_5") (pintype "passive"))
    )
    (net (code "15") (name "/T1-2") (class "Default")
      (node (ref "D4") (pin "2") (pinfunction "A_2") (pintype "passive"))
      (node (ref "D8") (pin "1") (pinfunction "C_1") (pintype "passive"))
      (node (ref "T1") (pin "8") (pinfunction "8_8") (pintype "passive"))
    )
    (net (code "16") (name "/T2-1") (class "Default")
      (node (ref "D10") (pin "1") (pinfunction "C_1") (pintype "passive"))
      (node (ref "D11") (pin "2") (pinfunction "A_2") (pintype "passive"))
      (node (ref "T2") (pin "5") (pinfunction "5_5") (pintype "passive"))
    )
    (net (code "17") (name "/T2-2") (class "Default")
      (node (ref "D12") (pin "2") (pinfunction "A_2") (pintype "passive"))
      (node (ref "D14") (pin "1") (pinfunction "C_1") (pintype "passive"))
      (node (ref "T2") (pin "8") (pinfunction "8_8") (pintype "passive"))
    )
    (net (code "18") (name "/VCC_IC") (class "Default")
      (node (ref "C17") (pin "1") (pinfunction "+_1") (pintype "passive"))
      (node (ref "C22") (pin "2") (pinfunction "2_2") (pintype "passive"))
      (node (ref "L4") (pin "1") (pinfunction "1_1") (pintype "passive"))
      (node (ref "TP11") (pin "1") (pinfunction "G9_1") (pintype "passive"))
      (node (ref "U1") (pin "12") (pinfunction "VCC_12") (pintype "power_in"))
    )
    (net (code "19") (name "/VCC_IC_1") (class "Default")
      (node (ref "C37") (pin "1") (pinfunction "+_1") (pintype "passive"))
      (node (ref "C42") (pin "2") (pinfunction "2_2") (pintype "passive"))
      (node (ref "L7") (pin "1") (pinfunction "1_1") (pintype "passive"))
      (node (ref "TP31") (pin "1") (pinfunction "G9_1") (pintype "passive"))
      (node (ref "U3") (pin "12") (pinfunction "VCC_12") (pintype "power_in"))
    )
    (net (code "20") (name "BAT") (class "Default")
      (node (ref "C1") (pin "1") (pinfunction "+_1") (pintype "passive"))
      (node (ref "C2") (pin "1") (pinfunction "+_1") (pintype "passive"))
      (node (ref "DD1") (pin "1") (pinfunction "VIN_1") (pintype "passive"))
      (node (ref "X2") (pin "1") (pinfunction "1_1") (pintype "passive"))
    )
    (net (code "21") (name "BAT_GND") (class "Default")
      (node (ref "C1") (pin "2") (pinfunction "-_2") (pintype "passive"))
      (node (ref "C10") (pin "2") (pinfunction "-_2") (pintype "passive"))
      (node (ref "C12") (pin "1") (pinfunction "1_1") (pintype "passive"))
      (node (ref "C14") (pin "2") (pinfunction "-_2") (pintype "passive"))
      (node (ref "C17") (pin "2") (pinfunction "-_2") (pintype "passive"))
      (node (ref "C18") (pin "2") (pinfunction "2_2") (pintype "passive"))
      (node (ref "C19") (pin "2") (pinfunction "2_2") (pintype "passive"))
      (node (ref "C2") (pin "2") (pinfunction "-_2") (pintype "passive"))
      (node (ref "C20") (pin "2") (pinfunction "-_2") (pintype "passive"))
      (node (ref "C21") (pin "1") (pinfunction "1_1") (pintype "passive"))
      (node (ref "C22") (pin "1") (pinfunction "1_1") (pintype "passive"))
      (node (ref "C23") (pin "1") (pinfunction "1_1") (pintype "passive"))
      (node (ref "C24") (pin "1") (pinfunction "1_1") (pintype "passive"))
      (node (ref "C3") (pin "2") (pinfunction "-_2") (pintype "passive"))
      (node (ref "C32") (pin "1") (pinfunction "1_1") (pintype "passive"))
      (node (ref "C33") (pin "2") (pinfunction "-_2") (pintype "passive"))
      (node (ref "C37") (pin "2") (pinfunction "-_2") (pintype "passive"))
      (node (ref "C38") (pin "2") (pinfunction "2_2") (pintype "passive"))
      (node (ref "C39") (pin "2") (pinfunction "2_2") (pintype "passive"))
      (node (ref "C4") (pin "2") (pinfunction "2_2") (pintype "passive"))
      (node (ref "C40") (pin "2") (pinfunction "-_2") (pintype "passive"))
      (node (ref "C41") (pin "1") (pinfunction "1_1") (pintype "passive"))
      (node (ref "C42") (pin "1") (pinfunction "1_1") (pintype "passive"))
      (node (ref "C43") (pin "1") (pinfunction "1_1") (pintype "passive"))
      (node (ref "C44") (pin "1") (pinfunction "1_1") (pintype "passive"))
      (node (ref "C5") (pin "2") (pinfunction "-_2") (pintype "passive"))
      (node (ref "C6") (pin "2") (pinfunction "-_2") (pintype "passive"))
      (node (ref "C8") (pin "2") (pinfunction "-_2") (pintype "passive"))
      (node (ref "C9") (pin "2") (pinfunction "-_2") (pintype "passive"))
      (node (ref "D6") (pin "2") (pinfunction "A_2") (pintype "passive"))
      (node (ref "DD1") (pin "3") (pinfunction "GND_3") (pintype "passive"))
      (node (ref "DD1") (pin "5") (pinfunction "ON/OFF_5") (pintype "passive"))
      (node (ref "L3") (pin "2") (pinfunction "2_2") (pintype "passive"))
      (node (ref "Q11") (pin "3") (pinfunction "C_3") (pintype "passive"))
      (node (ref "Q12") (pin "3") (pinfunction "C_3") (pintype "passive"))
      (node (ref "Q5") (pin "3") (pinfunction "C_3") (pintype "passive"))
      (node (ref "Q6") (pin "3") (pinfunction "C_3") (pintype "passive"))
      (node (ref "R1") (pin "1") (pinfunction "1_1") (pintype "passive"))
      (node (ref "R10") (pin "1") (pinfunction "1_1") (pintype "passive"))
      (node (ref "R13") (pin "2") (pinfunction "2_2") (pintype "passive"))
      (node (ref "R14") (pin "2") (pinfunction "2_2") (pintype "passive"))
      (node (ref "R16") (pin "2") (pinfunction "2_2") (pintype "passive"))
      (node (ref "R17") (pin "2") (pinfunction "2_2") (pintype "passive"))
      (node (ref "R19") (pin "1") (pinfunction "1_1") (pintype "passive"))
      (node (ref "R22") (pin "1") (pinfunction "1_1") (pintype "passive"))
      (node (ref "R23") (pin "1") (pinfunction "1_1") (pintype "passive"))
      (node (ref "R25") (pin "1") (pinfunction "1_1") (pintype "passive"))
      (node (ref "R3") (pin "1") (pinfunction "1_1") (pintype "passive"))
      (node (ref "R33") (pin "1") (pinfunction "1_1") (pintype "passive"))
      (node (ref "R38") (pin "2") (pinfunction "2_2") (pintype "passive"))
      (node (ref "R39") (pin "2") (pinfunction "2_2") (pintype "passive"))
      (node (ref "R40") (pin "1") (pinfunction "1_1") (pintype "passive"))
      (node (ref "R42") (pin "2") (pinfunction "2_2") (pintype "passive"))
      (node (ref "R43") (pin "2") (pinfunction "2_2") (pintype "passive"))
      (node (ref "R45") (pin "1") (pinfunction "1_1") (pintype "passive"))
      (node (ref "R46") (pin "1") (pinfunction "1_1") (pintype "passive"))
      (node (ref "R48") (pin "1") (pinfunction "1_1") (pintype "passive"))
      (node (ref "U1") (pin "7") (pinfunction "GND_7") (pintype "power_in"))
      (node (ref "U2") (pin "3") (pinfunction "A_3") (pintype "passive"))
      (node (ref "U3") (pin "7") (pinfunction "GND_7") (pintype "power_in"))
      (node (ref "U4") (pin "3") (pinfunction "A_3") (pintype "passive"))
      (node (ref "VD1") (pin "1") (pinfunction "C_1") (pintype "passive"))
      (node (ref "VD2") (pin "1") (pinfunction "C_1") (pintype "passive"))
      (node (ref "VD3") (pin "2") (pinfunction "A_2") (pintype "passive"))
      (node (ref "VD4") (pin "1") (pinfunction "C_1") (pintype "passive"))
      (node (ref "VD5") (pin "1") (pinfunction "C_1") (pintype "passive"))
      (node (ref "VD6") (pin "2") (pinfunction "A_2") (pintype "passive"))
      (node (ref "X1") (pin "2") (pinfunction "2_2") (pintype "passive"))
      (node (ref "X2") (pin "2") (pinfunction "2_2") (pintype "passive"))
      (node (ref "X3") (pin "2") (pinfunction "2_2") (pintype "passive"))
      (node (ref "X5") (pin "2") (pinfunction "2_2") (pintype "passive"))
    )
    (net (code "22") (name "GND_1") (class "Default")
      (node (ref "C25") (pin "2") (pinfunction "-_2") (pintype "passive"))
      (node (ref "C26") (pin "2") (pinfunction "-_2") (pintype "passive"))
      (node (ref "L6") (pin "2") (pinfunction "2_2") (pintype "passive"))
      (node (ref "R26") (pin "1") (pinfunction "1_1") (pintype "passive"))
      (node (ref "X4") (pin "2") (pinfunction "2_2") (pintype "passive"))
      (node (ref "X6") (pin "2") (pinfunction "2_2") (pintype "passive"))
    )
    (net (code "23") (name "Net-(C7-+)") (class "Default")
      (node (ref "C7") (pin "1") (pinfunction "+_1") (pintype "passive"))
      (node (ref "D2") (pin "1") (pinfunction "C_1") (pintype "passive"))
      (node (ref "D4") (pin "1") (pinfunction "C_1") (pintype "passive"))
      (node (ref "L1") (pin "1") (pinfunction "1_1") (pintype "passive"))
    )
    (net (code "24") (name "Net-(C7--)") (class "Default")
      (node (ref "C7") (pin "2") (pinfunction "-_2") (pintype "passive"))
      (node (ref "D1") (pin "2") (pinfunction "A_2") (pintype "passive"))
      (node (ref "D8") (pin "2") (pinfunction "A_2") (pintype "passive"))
      (node (ref "L3") (pin "1") (pinfunction "1_1") (pintype "passive"))
    )
    (net (code "25") (name "Net-(C10-+)") (class "Default")
      (node (ref "C10") (pin "1") (pinfunction "+_1") (pintype "passive"))
      (node (ref "C3") (pin "1") (pinfunction "+_1") (pintype "passive"))
      (node (ref "C4") (pin "1") (pinfunction "1_1") (pintype "passive"))
      (node (ref "C8") (pin "1") (pinfunction "+_1") (pintype "passive"))
      (node (ref "C9") (pin "1") (pinfunction "+_1") (pintype "passive"))
      (node (ref "D3") (pin "2") (pinfunction "A_2") (pintype "passive"))
      (node (ref "L2") (pin "2") (pinfunction "2_2") (pintype "passive"))
      (node (ref "R2") (pin "2") (pinfunction "2_2") (pintype "passive"))
    )
    (net (code "26") (name "Net-(C11-Pad1)") (class "Default")
      (node (ref "C11") (pin "1") (pinfunction "1_1") (pintype "passive"))
      (node (ref "R4") (pin "2") (pinfunction "2_2") (pintype "passive"))
    )
    (net (code "27") (name "Net-(C15-Pad2)") (class "Default")
      (node (ref "C15") (pin "2") (pinfunction "2_2") (pintype "passive"))
      (node (ref "R6") (pin "1") (pinfunction "1_1") (pintype "passive"))
    )
    (net (code "28") (name "Net-(C20-+)") (class "Default")
      (node (ref "C20") (pin "1") (pinfunction "+_1") (pintype "passive"))
      (node (ref "C21") (pin "2") (pinfunction "2_2") (pintype "passive"))
      (node (ref "R15") (pin "2") (pinfunction "2_2") (pintype "passive"))
      (node (ref "R18") (pin "2") (pinfunction "2_2") (pintype "passive"))
      (node (ref "TP15") (pin "1") (pinfunction "G9_1") (pintype "passive"))
      (node (ref "U1") (pin "13") (pinfunction "OUTPUT_CTRL_13") (pintype "input"))
      (node (ref "U1") (pin "14") (pinfunction "REF_14") (pintype "output"))
    )
    (net (code "29") (name "Net-(C27-+)") (class "Default")
      (node (ref "C27") (pin "1") (pinfunction "+_1") (pintype "passive"))
      (node (ref "D11") (pin "1") (pinfunction "C_1") (pintype "passive"))
      (node (ref "D12") (pin "1") (pinfunction "C_1") (pintype "passive"))
      (node (ref "L5") (pin "1") (pinfunction "1_1") (pintype "passive"))
    )
    (net (code "30") (name "Net-(C27--)") (class "Default")
      (node (ref "C27") (pin "2") (pinfunction "-_2") (pintype "passive"))
      (node (ref "D10") (pin "2") (pinfunction "A_2") (pintype "passive"))
      (node (ref "D14") (pin "2") (pinfunction "A_2") (pintype "passive"))
      (node (ref "L6") (pin "1") (pinfunction "1_1") (pintype "passive"))
    )
    (net (code "31") (name "Net-(C31-Pad1)") (class "Default")
      (node (ref "C31") (pin "1") (pinfunction "1_1") (pintype "passive"))
      (node (ref "R27") (pin "2") (pinfunction "2_2") (pintype "passive"))
    )
    (net (code "32") (name "Net-(C35-Pad2)") (class "Default")
      (node (ref "C35") (pin "2") (pinfunction "2_2") (pintype "passive"))
      (node (ref "R28") (pin "1") (pinfunction "1_1") (pintype "passive"))
    )
    (net (code "33") (name "Net-(C40-+)") (class "Default")
      (node (ref "C40") (pin "1") (pinfunction "+_1") (pintype "passive"))
      (node (ref "C41") (pin "2") (pinfunction "2_2") (pintype "passive"))
      (node (ref "R41") (pin "2") (pinfunction "2_2") (pintype "passive"))
      (node (ref "R44") (pin "2") (pinfunction "2_2") (pintype "passive"))
      (node (ref "TP33") (pin "1") (pinfunction "G9_1") (pintype "passive"))
      (node (ref "U3") (pin "13") (pinfunction "OUTPUT_CTRL_13") (pintype "input"))
      (node (ref "U3") (pin "14") (pinfunction "REF_14") (pintype "output"))
    )
    (net (code "34") (name "Net-(D5-K)") (class "Default")
      (node (ref "D5") (pin "2") (pinfunction "K_2") (pintype "passive"))
      (node (ref "R3") (pin "2") (pinfunction "2_2") (pintype "passive"))
    )
    (net (code "35") (name "Net-(D6-C)") (class "Default")
      (node (ref "D6") (pin "1") (pinfunction "C_1") (pintype "passive"))
      (node (ref "DD1") (pin "2") (pinfunction "OUT_2") (pintype "passive"))
      (node (ref "L2") (pin "1") (pinfunction "1_1") (pintype "passive"))
    )
    (net (code "36") (name "Net-(D7-A)") (class "Default")
      (node (ref "D7") (pin "2") (pinfunction "A_2") (pintype "passive"))
      (node (ref "X1") (pin "1") (pinfunction "1_1") (pintype "passive"))
    )
    (net (code "37") (name "Net-(D9-A)") (class "Default")
      (node (ref "C13") (pin "2") (pinfunction "2_2") (pintype "passive"))
      (node (ref "C16") (pin "1") (pinfunction "1_1") (pintype "passive"))
      (node (ref "D9") (pin "1") (pinfunction "A_1") (pintype "passive"))
      (node (ref "R7") (pin "2") (pinfunction "2_2") (pintype "passive"))
      (node (ref "R9") (pin "1") (pinfunction "1_1") (pintype "passive"))
      (node (ref "TP4") (pin "1") (pinfunction "G9_1") (pintype "passive"))
      (node (ref "U1") (pin "3") (pinfunction "FEEDBACK_3") (pintype "input"))
    )
    (net (code "38") (name "Net-(D9-K)") (class "Default")
      (node (ref "D9") (pin "2") (pinfunction "K_2") (pintype "passive"))
      (node (ref "R10") (pin "2") (pinfunction "2_2") (pintype "passive"))
    )
    (net (code "39") (name "Net-(D13-K)") (class "Default")
      (node (ref "D13") (pin "2") (pinfunction "K_2") (pintype "passive"))
      (node (ref "R26") (pin "2") (pinfunction "2_2") (pintype "passive"))
    )
    (net (code "40") (name "Net-(D15-A)") (class "Default")
      (node (ref "C34") (pin "2") (pinfunction "2_2") (pintype "passive"))
      (node (ref "C36") (pin "1") (pinfunction "1_1") (pintype "passive"))
      (node (ref "D15") (pin "1") (pinfunction "A_1") (pintype "passive"))
      (node (ref "R30") (pin "2") (pinfunction "2_2") (pintype "passive"))
      (node (ref "R32") (pin "1") (pinfunction "1_1") (pintype "passive"))
      (node (ref "TP23") (pin "1") (pinfunction "G9_1") (pintype "passive"))
      (node (ref "U3") (pin "3") (pinfunction "FEEDBACK_3") (pintype "input"))
    )
    (net (code "41") (name "Net-(D15-K)") (class "Default")
      (node (ref "D15") (pin "2") (pinfunction "K_2") (pintype "passive"))
      (node (ref "R33") (pin "2") (pinfunction "2_2") (pintype "passive"))
    )
    (net (code "42") (name "Net-(DD1-FEEDBACK)") (class "Default")
      (node (ref "DD1") (pin "4") (pinfunction "FEEDBACK_4") (pintype "passive"))
      (node (ref "R1") (pin "2") (pinfunction "2_2") (pintype "passive"))
      (node (ref "R2") (pin "1") (pinfunction "1_1") (pintype "passive"))
    )
    (net (code "43") (name "Net-(Q1-B)") (class "Default")
      (node (ref "Q1") (pin "1") (pinfunction "B_1") (pintype "passive"))
      (node (ref "Q5") (pin "1") (pinfunction "B_1") (pintype "passive"))
      (node (ref "R11") (pin "1") (pinfunction "1_1") (pintype "passive"))
      (node (ref "R22") (pin "2") (pinfunction "2_2") (pintype "passive"))
      (node (ref "TP9") (pin "1") (pinfunction "G9_1") (pintype "passive"))
    )
    (net (code "44") (name "Net-(Q1-E)") (class "Default")
      (node (ref "Q1") (pin "2") (pinfunction "E_2") (pintype "passive"))
      (node (ref "Q5") (pin "2") (pinfunction "E_2") (pintype "passive"))
      (node (ref "R12") (pin "1") (pinfunction "1_1") (pintype "passive"))
    )
    (net (code "45") (name "Net-(Q2-G)") (class "Default")
      (node (ref "Q2") (pin "1") (pinfunction "G_1") (pintype "passive"))
      (node (ref "R12") (pin "2") (pinfunction "2_2") (pintype "passive"))
      (node (ref "TP10") (pin "1") (pinfunction "G9_1") (pintype "passive"))
    )
    (net (code "46") (name "Net-(Q2-S)") (class "Default")
      (node (ref "C23") (pin "2") (pinfunction "2_2") (pintype "passive"))
      (node (ref "Q2") (pin "3") (pinfunction "S_3") (pintype "passive"))
      (node (ref "Q4") (pin "3") (pinfunction "S_3") (pintype "passive"))
      (node (ref "R24") (pin "2") (pinfunction "2_2") (pintype "passive"))
      (node (ref "R25") (pin "2") (pinfunction "2_2") (pintype "passive"))
      (node (ref "TP18") (pin "1") (pinfunction "G9_1") (pintype "passive"))
    )
    (net (code "47") (name "Net-(Q3-B)") (class "Default")
      (node (ref "Q3") (pin "1") (pinfunction "B_1") (pintype "passive"))
      (node (ref "Q6") (pin "1") (pinfunction "B_1") (pintype "passive"))
      (node (ref "R20") (pin "1") (pinfunction "1_1") (pintype "passive"))
      (node (ref "R23") (pin "2") (pinfunction "2_2") (pintype "passive"))
      (node (ref "TP14") (pin "1") (pinfunction "G9_1") (pintype "passive"))
    )
    (net (code "48") (name "Net-(Q3-E)") (class "Default")
      (node (ref "Q3") (pin "2") (pinfunction "E_2") (pintype "passive"))
      (node (ref "Q6") (pin "2") (pinfunction "E_2") (pintype "passive"))
      (node (ref "R21") (pin "1") (pinfunction "1_1") (pintype "passive"))
    )
    (net (code "49") (name "Net-(Q4-G)") (class "Default")
      (node (ref "Q4") (pin "1") (pinfunction "G_1") (pintype "passive"))
      (node (ref "R21") (pin "2") (pinfunction "2_2") (pintype "passive"))
      (node (ref "TP13") (pin "1") (pinfunction "G9_1") (pintype "passive"))
    )
    (net (code "50") (name "Net-(Q8-G)") (class "Default")
      (node (ref "Q8") (pin "1") (pinfunction "G_1") (pintype "passive"))
      (node (ref "R35") (pin "2") (pinfunction "2_2") (pintype "passive"))
      (node (ref "TP27") (pin "1") (pinfunction "G9_1") (pintype "passive"))
    )
    (net (code "51") (name "Net-(Q10-G)") (class "Default")
      (node (ref "Q10") (pin "1") (pinfunction "G_1") (pintype "passive"))
      (node (ref "R37") (pin "2") (pinfunction "2_2") (pintype "passive"))
      (node (ref "TP29") (pin "1") (pinfunction "G9_1") (pintype "passive"))
    )
    (net (code "52") (name "Net-(Q10-S)") (class "Default")
      (node (ref "C43") (pin "2") (pinfunction "2_2") (pintype "passive"))
      (node (ref "Q10") (pin "3") (pinfunction "S_3") (pintype "passive"))
      (node (ref "Q8") (pin "3") (pinfunction "S_3") (pintype "passive"))
      (node (ref "R47") (pin "2") (pinfunction "2_2") (pintype "passive"))
      (node (ref "R48") (pin "2") (pinfunction "2_2") (pintype "passive"))
      (node (ref "TP36") (pin "1") (pinfunction "G9_1") (pintype "passive"))
    )
    (net (code "53") (name "Net-(Q11-B)") (class "Default")
      (node (ref "Q11") (pin "1") (pinfunction "B_1") (pintype "passive"))
      (node (ref "Q7") (pin "1") (pinfunction "B_1") (pintype "passive"))
      (node (ref "R34") (pin "1") (pinfunction "1_1") (pintype "passive"))
      (node (ref "R40") (pin "2") (pinfunction "2_2") (pintype "passive"))
      (node (ref "TP25") (pin "1") (pinfunction "G9_1") (pintype "passive"))
    )
    (net (code "54") (name "Net-(Q11-E)") (class "Default")
      (node (ref "Q11") (pin "2") (pinfunction "E_2") (pintype "passive"))
      (node (ref "Q7") (pin "2") (pinfunction "E_2") (pintype "passive"))
      (node (ref "R35") (pin "1") (pinfunction "1_1") (pintype "passive"))
    )
    (net (code "55") (name "Net-(Q12-B)") (class "Default")
      (node (ref "Q12") (pin "1") (pinfunction "B_1") (pintype "passive"))
      (node (ref "Q9") (pin "1") (pinfunction "B_1") (pintype "passive"))
      (node (ref "R36") (pin "1") (pinfunction "1_1") (pintype "passive"))
      (node (ref "R46") (pin "2") (pinfunction "2_2") (pintype "passive"))
      (node (ref "TP30") (pin "1") (pinfunction "G9_1") (pintype "passive"))
    )
    (net (code "56") (name "Net-(Q12-E)") (class "Default")
      (node (ref "Q12") (pin "2") (pinfunction "E_2") (pintype "passive"))
      (node (ref "Q9") (pin "2") (pinfunction "E_2") (pintype "passive"))
      (node (ref "R37") (pin "1") (pinfunction "1_1") (pintype "passive"))
    )
    (net (code "57") (name "Net-(T1-Pad6)") (class "Default")
      (node (ref "T1") (pin "6") (pinfunction "6_6") (pintype "passive"))
      (node (ref "T1") (pin "7") (pinfunction "7_7") (pintype "passive"))
    )
    (net (code "58") (name "Net-(T2-Pad6)") (class "Default")
      (node (ref "T2") (pin "6") (pinfunction "6_6") (pintype "passive"))
      (node (ref "T2") (pin "7") (pinfunction "7_7") (pintype "passive"))
    )
    (net (code "59") (name "Net-(TP2-G9)") (class "Default")
      (node (ref "C13") (pin "1") (pinfunction "1_1") (pintype "passive"))
      (node (ref "R15") (pin "1") (pinfunction "1_1") (pintype "passive"))
      (node (ref "R16") (pin "1") (pinfunction "1_1") (pintype "passive"))
      (node (ref "R7") (pin "1") (pinfunction "1_1") (pintype "passive"))
      (node (ref "TP2") (pin "1") (pinfunction "G9_1") (pintype "passive"))
      (node (ref "U1") (pin "2") (pinfunction "1IN-_2") (pintype "input"))
    )
    (net (code "60") (name "Net-(TP3-G9)") (class "Default")
      (node (ref "C19") (pin "1") (pinfunction "1_1") (pintype "passive"))
      (node (ref "R14") (pin "1") (pinfunction "1_1") (pintype "passive"))
      (node (ref "R5") (pin "2") (pinfunction "2_2") (pintype "passive"))
      (node (ref "TP3") (pin "1") (pinfunction "G9_1") (pintype "passive"))
      (node (ref "U1") (pin "16") (pinfunction "2IN+_16") (pintype "input"))
    )
    (net (code "61") (name "Net-(TP7-G9)") (class "Default")
      (node (ref "C16") (pin "2") (pinfunction "2_2") (pintype "passive"))
      (node (ref "R17") (pin "1") (pinfunction "1_1") (pintype "passive"))
      (node (ref "R18") (pin "1") (pinfunction "1_1") (pintype "passive"))
      (node (ref "R9") (pin "2") (pinfunction "2_2") (pintype "passive"))
      (node (ref "TP7") (pin "1") (pinfunction "G9_1") (pintype "passive"))
      (node (ref "U1") (pin "15") (pinfunction "2IN-_15") (pintype "input"))
      (node (ref "U2") (pin "1") (pinfunction "C_1") (pintype "passive"))
      (node (ref "U2") (pin "2") (pinfunction "REF_2") (pintype "passive"))
    )
    (net (code "62") (name "Net-(TP8-G9)") (class "Default")
      (node (ref "R13") (pin "1") (pinfunction "1_1") (pintype "passive"))
      (node (ref "TP8") (pin "1") (pinfunction "G9_1") (pintype "passive"))
      (node (ref "U1") (pin "6") (pinfunction "RT_6") (pintype "passive"))
    )
    (net (code "63") (name "Net-(TP12-G9)") (class "Default")
      (node (ref "C18") (pin "1") (pinfunction "1_1") (pintype "passive"))
      (node (ref "TP12") (pin "1") (pinfunction "G9_1") (pintype "passive"))
      (node (ref "U1") (pin "5") (pinfunction "CT_5") (pintype "passive"))
    )
    (net (code "64") (name "Net-(TP20-G9)") (class "Default")
      (node (ref "C34") (pin "1") (pinfunction "1_1") (pintype "passive"))
      (node (ref "R30") (pin "1") (pinfunction "1_1") (pintype "passive"))
      (node (ref "R41") (pin "1") (pinfunction "1_1") (pintype "passive"))
      (node (ref "R42") (pin "1") (pinfunction "1_1") (pintype "passive"))
      (node (ref "TP20") (pin "1") (pinfunction "G9_1") (pintype "passive"))
      (node (ref "U3") (pin "2") (pinfunction "1IN-_2") (pintype "input"))
    )
    (net (code "65") (name "Net-(TP21-G9)") (class "Default")
      (node (ref "C39") (pin "1") (pinfunction "1_1") (pintype "passive"))
      (node (ref "R29") (pin "2") (pinfunction "2_2") (pintype "passive"))
      (node (ref "R39") (pin "1") (pinfunction "1_1") (pintype "passive"))
      (node (ref "TP21") (pin "1") (pinfunction "G9_1") (pintype "passive"))
      (node (ref "U3") (pin "16") (pinfunction "2IN+_16") (pintype "input"))
    )
    (net (code "66") (name "Net-(TP26-G9)") (class "Default")
      (node (ref "C36") (pin "2") (pinfunction "2_2") (pintype "passive"))
      (node (ref "R32") (pin "2") (pinfunction "2_2") (pintype "passive"))
      (node (ref "R43") (pin "1") (pinfunction "1_1") (pintype "passive"))
      (node (ref "R44") (pin "1") (pinfunction "1_1") (pintype "passive"))
      (node (ref "TP26") (pin "1") (pinfunction "G9_1") (pintype "passive"))
      (node (ref "U3") (pin "15") (pinfunction "2IN-_15") (pintype "input"))
      (node (ref "U4") (pin "1") (pinfunction "C_1") (pintype "passive"))
      (node (ref "U4") (pin "2") (pinfunction "REF_2") (pintype "passive"))
    )
    (net (code "67") (name "Net-(TP28-G9)") (class "Default")
      (node (ref "R38") (pin "1") (pinfunction "1_1") (pintype "passive"))
      (node (ref "TP28") (pin "1") (pinfunction "G9_1") (pintype "passive"))
      (node (ref "U3") (pin "6") (pinfunction "RT_6") (pintype "passive"))
    )
    (net (code "68") (name "Net-(TP32-G9)") (class "Default")
      (node (ref "C38") (pin "1") (pinfunction "1_1") (pintype "passive"))
      (node (ref "TP32") (pin "1") (pinfunction "G9_1") (pintype "passive"))
      (node (ref "U3") (pin "5") (pinfunction "CT_5") (pintype "passive"))
    )
    (net (code "69") (name "Net-(U1-C1)") (class "Default")
      (node (ref "R8") (pin "1") (pinfunction "1_1") (pintype "passive"))
      (node (ref "U1") (pin "11") (pinfunction "C2_11") (pintype "passive"))
      (node (ref "U1") (pin "8") (pinfunction "C1_8") (pintype "passive"))
    )
    (net (code "70") (name "Net-(U1-DTC)") (class "Default")
      (node (ref "R19") (pin "2") (pinfunction "2_2") (pintype "passive"))
      (node (ref "U1") (pin "4") (pinfunction "DTC_4") (pintype "input"))
    )
    (net (code "71") (name "Net-(U3-C1)") (class "Default")
      (node (ref "R31") (pin "1") (pinfunction "1_1") (pintype "passive"))
      (node (ref "U3") (pin "11") (pinfunction "C2_11") (pintype "passive"))
      (node (ref "U3") (pin "8") (pinfunction "C1_8") (pintype "passive"))
    )
    (net (code "72") (name "Net-(U3-DTC)") (class "Default")
      (node (ref "R45") (pin "2") (pinfunction "2_2") (pintype "passive"))
      (node (ref "U3") (pin "4") (pinfunction "DTC_4") (pintype "input"))
    )
  )
)
